# att_17db.net
KiCad netlist of a schematic drawn in Altium Designer
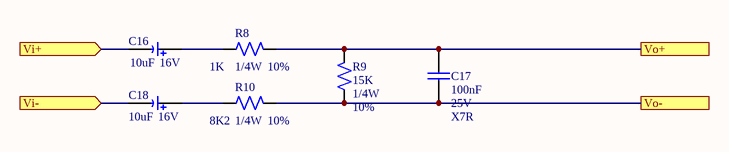
[diagram p0: att_17db.SchDoc]

(export (version "E")
  (design (tool "Eeschema 10.0.6"))
  (components
    (comp (ref "C16")
      (value "Capacitor polarizado")
      (footprint "CAP_Electrolytic")
      (fields (field (name "VALOR") "10uF") (field (name "TENSION") "16V"))
      (libsource (lib "Sch_Comunes") (part "Capacitor polarizado"))
    )
    (comp (ref "C17")
      (value "Capacitor")
      (footprint "C0805")
      (description "Capacitor de placas paralelas")
      (fields (field (name "VALOR") "100nF") (field (name "TENSION") "25V") (field (name "TOLERANCIA") "X7R"))
      (libsource (lib "Sch_Comunes") (part "Capacitor"))
    )
    (comp (ref "C18")
      (value "Capacitor polarizado")
      (footprint "CAP_Electrolytic")
      (fields (field (name "VALOR") "10uF") (field (name "TENSION") "16V"))
      (libsource (lib "Sch_Comunes") (part "Capacitor polarizado"))
    )
    (comp (ref "R8")
      (value "Resistor")
      (footprint "R0805")
      (description "Resistencia")
      (fields (field (name "VALOR") "1K") (field (name "POTENCIA") "1/4W") (field (name "TOLERANCIA") "10%"))
      (libsource (lib "sch_comunes") (part "Resistor"))
    )
    (comp (ref "R9")
      (value "Resistor")
      (footprint "R0805")
      (description "Resistencia")
      (fields (field (name "VALOR") "15K") (field (name "POTENCIA") "1/4W") (field (name "TOLERANCIA") "10%"))
      (libsource (lib "sch_comunes") (part "Resistor"))
    )
    (comp (ref "R10")
      (value "Resistor")
      (footprint "R0805")
      (description "Resistencia")
      (fields (field (name "VALOR") "8K2") (field (name "POTENCIA") "1/4W") (field (name "TOLERANCIA") "10%"))
      (libsource (lib "sch_comunes") (part "Resistor"))
    )
  )
  (nets
    (net (code "1") (name "/Vi+") (class "Default")
      (node (ref "C16") (pin "2") (pinfunction "2_2") (pintype "passive"))
    )
    (net (code "2") (name "/Vi-") (class "Default")
      (node (ref "C18") (pin "2") (pinfunction "2_2") (pintype "passive"))
    )
    (net (code "3") (name "/Vo+") (class "Default")
      (node (ref "C17") (pin "1") (pinfunction "1_1") (pintype "passive"))
      (node (ref "R8") (pin "2") (pinfunction "2_2") (pintype "passive"))
      (node (ref "R9") (pin "2") (pinfunction "2_2") (pintype "passive"))
    )
    (net (code "4") (name "/Vo-") (class "Default")
      (node (ref "C17") (pin "2") (pinfunction "2_2") (pintype "passive"))
      (node (ref "R10") (pin "2") (pinfunction "2_2") (pintype "passive"))
      (node (ref "R9") (pin "1") (pinfunction "1_1") (pintype "passive"))
    )
    (net (code "5") (name "Net-(C16-Pad1)") (class "Default")
      (node (ref "C16") (pin "1") (pinfunction "1_1") (pintype "passive"))
      (node (ref "R8") (pin "1") (pinfunction "1_1") (pintype "passive"))
    )
    (net (code "6") (name "Net-(C18-Pad1)") (class "Default")
      (node (ref "C18") (pin "1") (pinfunction "1_1") (pintype "passive"))
      (node (ref "R10") (pin "1") (pinfunction "1_1") (pintype "passive"))
    )
  )
)
